# canAIReSensor.net
KiCad netlist of a schematic drawn in EAGLE
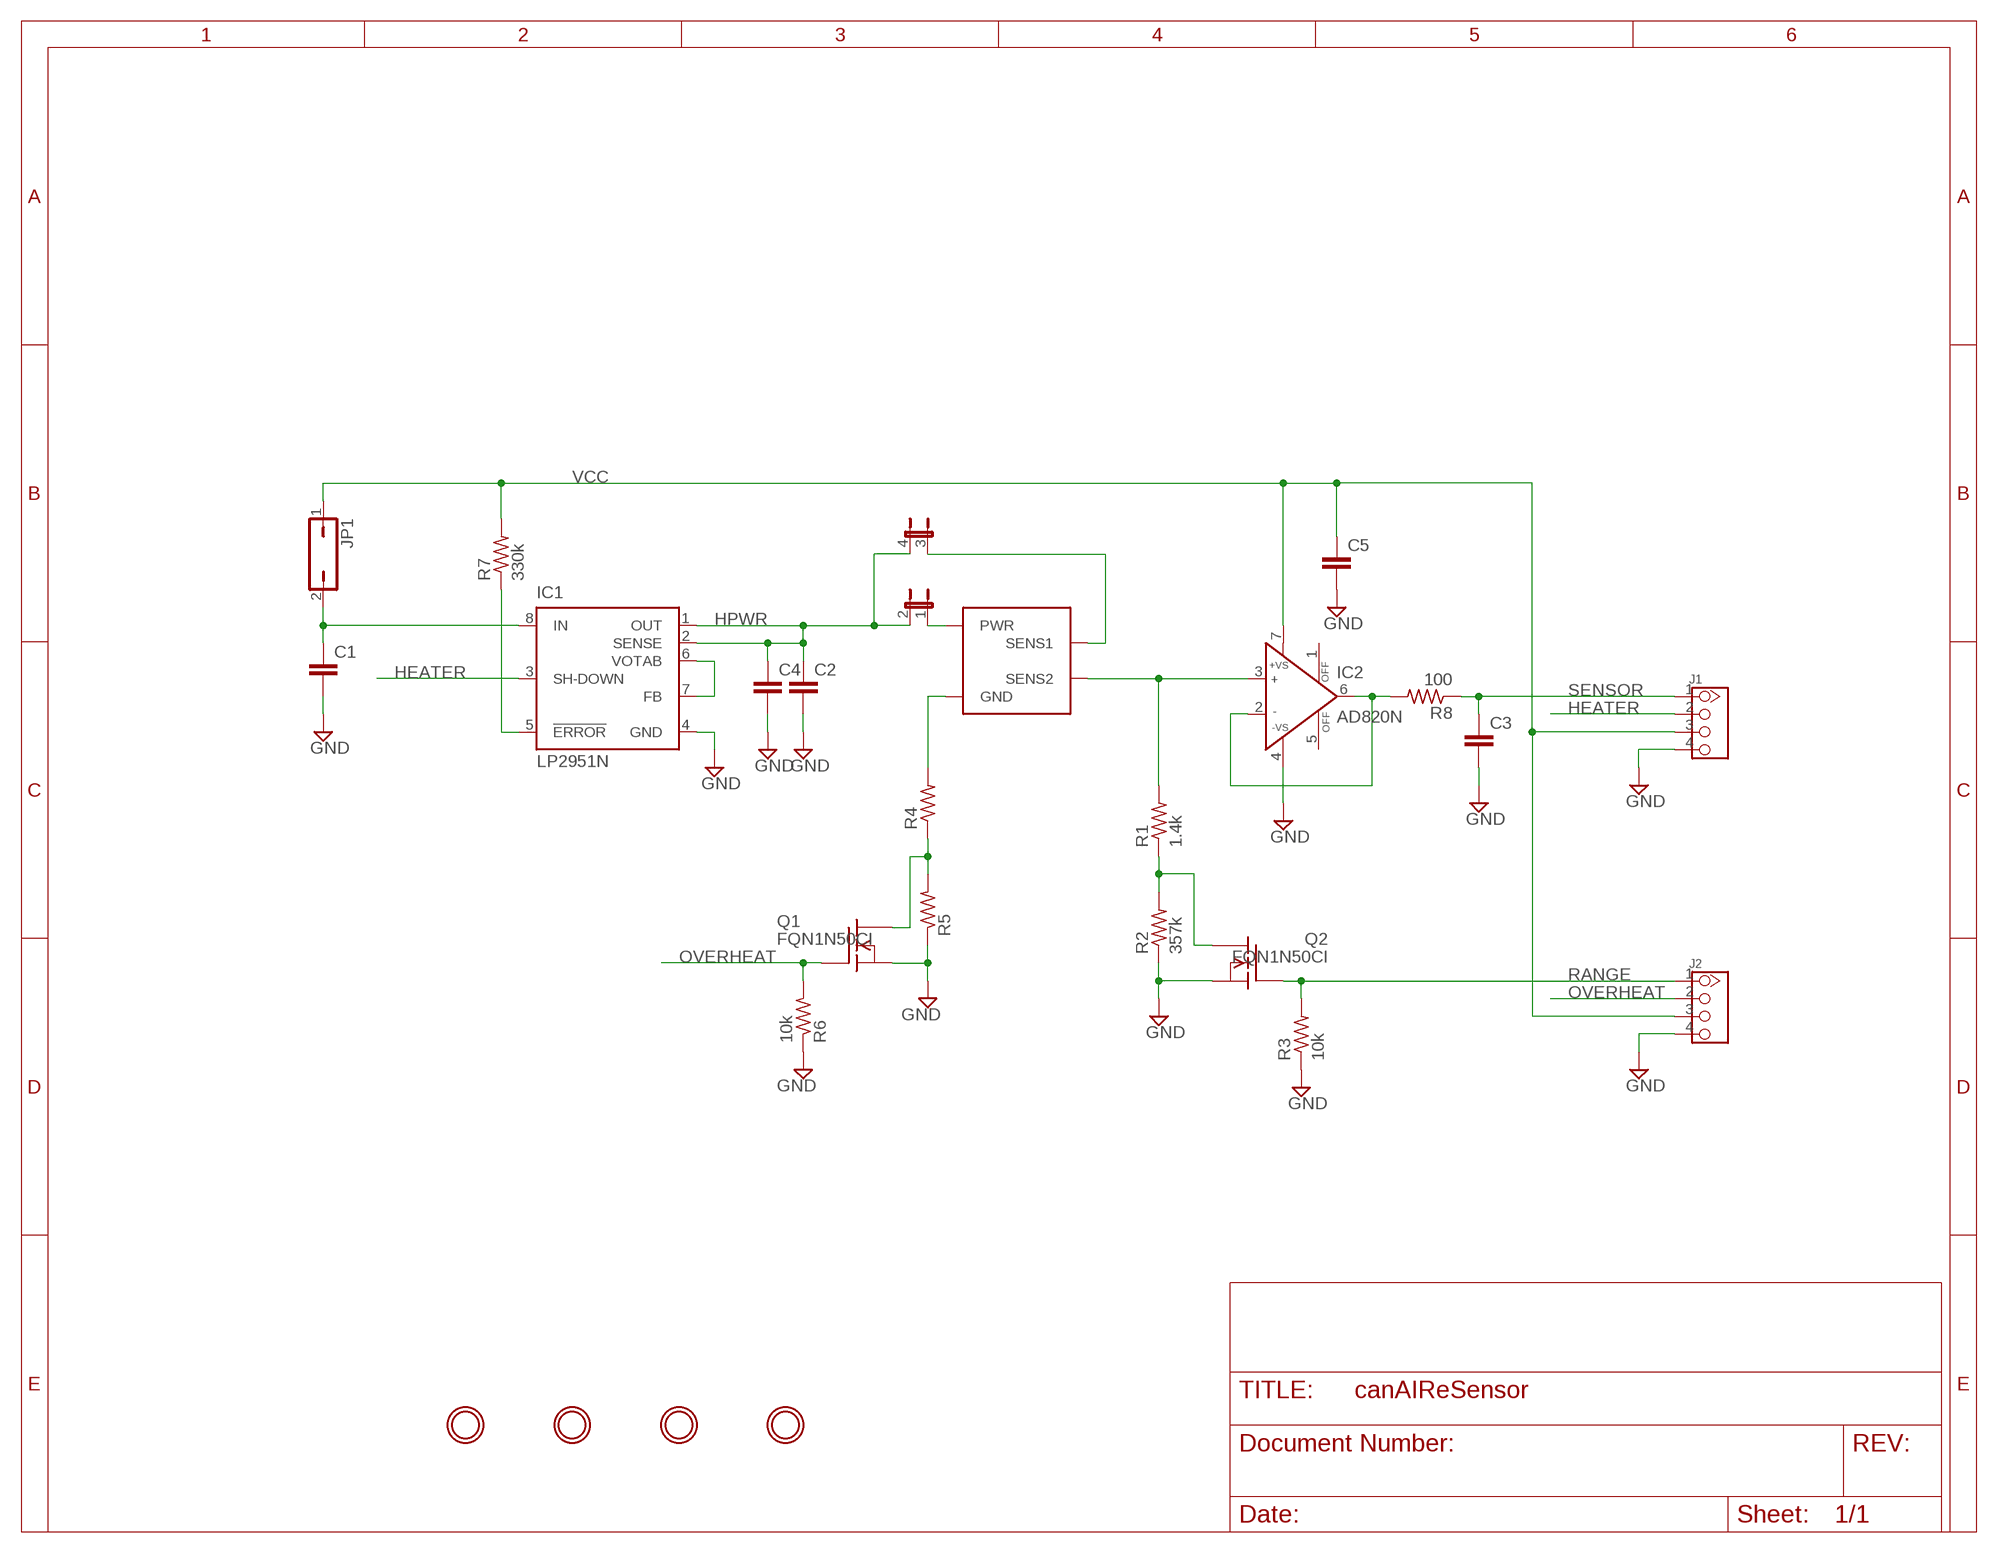
[diagram p0: schematic, sheet 1]

(export (version "E")
  (design (tool "Eeschema 10.0.6"))
  (components
    (comp (ref "C1")
      (value "C-EU050-024X044")
      (footprint "eagle-import:C050-024X044")
      (libsource (lib "eagle-import") (part "C-EU050-024X044"))
    )
    (comp (ref "C2")
      (value "C-EU050-024X044")
      (footprint "eagle-import:C050-024X044")
      (libsource (lib "eagle-import") (part "C-EU050-024X044"))
    )
    (comp (ref "C3")
      (value "C-EU050-024X044")
      (footprint "eagle-import:C050-024X044")
      (libsource (lib "eagle-import") (part "C-EU050-024X044"))
    )
    (comp (ref "C4")
      (value "C-EU050-024X044")
      (footprint "eagle-import:C050-024X044")
      (libsource (lib "eagle-import") (part "C-EU050-024X044"))
    )
    (comp (ref "C5")
      (value "C-EU050-024X044")
      (footprint "eagle-import:C050-024X044")
      (libsource (lib "eagle-import") (part "C-EU050-024X044"))
    )
    (comp (ref "IC1")
      (value "LP2951N")
      (footprint "eagle-import:DIL08")
      (libsource (lib "eagle-import") (part "LP2951N"))
    )
    (comp (ref "IC2")
      (value "AD820N")
      (footprint "eagle-import:DIL08")
      (libsource (lib "eagle-import") (part "AD820N"))
    )
    (comp (ref "J1")
      (value "TWIG-4P-2.0'90D'")
      (footprint "eagle-import:4P-2.0-90D")
      (libsource (lib "eagle-import") (part "TWIG-4P-2.0'90D'"))
    )
    (comp (ref "J2")
      (value "TWIG-4P-2.0'90D'")
      (footprint "eagle-import:4P-2.0-90D")
      (libsource (lib "eagle-import") (part "TWIG-4P-2.0'90D'"))
    )
    (comp (ref "JP1")
      (value "JP1Q")
      (footprint "eagle-import:JP1")
      (libsource (lib "eagle-import") (part "JP1Q"))
    )
    (comp (ref "JP4")
      (value "JP2QE")
      (footprint "eagle-import:JP2Q")
      (libsource (lib "eagle-import") (part "JP2QE"))
    )
    (comp (ref "Q1")
      (value "FQN1N50CI")
      (footprint "eagle-import:TO92-INLINE")
      (libsource (lib "eagle-import") (part "FQN1N50CI"))
    )
    (comp (ref "Q2")
      (value "FQN1N50CI")
      (footprint "eagle-import:TO92-INLINE")
      (libsource (lib "eagle-import") (part "FQN1N50CI"))
    )
    (comp (ref "R1")
      (value "1.4k")
      (footprint "eagle-import:0204_7")
      (libsource (lib "eagle-import") (part "R-US_0204/7"))
    )
    (comp (ref "R2")
      (value "357k")
      (footprint "eagle-import:0204_7")
      (libsource (lib "eagle-import") (part "R-US_0204/7"))
    )
    (comp (ref "R3")
      (value "10k")
      (footprint "eagle-import:0204_7")
      (libsource (lib "eagle-import") (part "R-US_0204/7"))
    )
    (comp (ref "R4")
      (value "R-US_0204/7")
      (footprint "eagle-import:0204_7")
      (libsource (lib "eagle-import") (part "R-US_0204/7"))
    )
    (comp (ref "R5")
      (value "R-US_0204/7")
      (footprint "eagle-import:0204_7")
      (libsource (lib "eagle-import") (part "R-US_0204/7"))
    )
    (comp (ref "R6")
      (value "10k")
      (footprint "eagle-import:0204_7")
      (libsource (lib "eagle-import") (part "R-US_0204/7"))
    )
    (comp (ref "R7")
      (value "330k")
      (footprint "eagle-import:0204_7")
      (libsource (lib "eagle-import") (part "R-US_0204/7"))
    )
    (comp (ref "R8")
      (value "100")
      (footprint "eagle-import:0204_7")
      (libsource (lib "eagle-import") (part "R-US_0204/7"))
    )
    (comp (ref "U$1")
      (value "E2V_MICS")
      (footprint "eagle-import:E2V_MICS")
      (libsource (lib "eagle-import") (part "E2V_MICS"))
    )
    (comp (ref "U$2")
      (value "MOUNTINGHOLE2.5")
      (footprint "eagle-import:MOUNTINGHOLE_2.5_PLATED")
      (libsource (lib "eagle-import") (part "MOUNTINGHOLE2.5"))
    )
    (comp (ref "U$3")
      (value "MOUNTINGHOLE2.5")
      (footprint "eagle-import:MOUNTINGHOLE_2.5_PLATED")
      (libsource (lib "eagle-import") (part "MOUNTINGHOLE2.5"))
    )
    (comp (ref "U$4")
      (value "MOUNTINGHOLE2.5")
      (footprint "eagle-import:MOUNTINGHOLE_2.5_PLATED")
      (libsource (lib "eagle-import") (part "MOUNTINGHOLE2.5"))
    )
    (comp (ref "U$5")
      (value "MOUNTINGHOLE2.5")
      (footprint "eagle-import:MOUNTINGHOLE_2.5_PLATED")
      (libsource (lib "eagle-import") (part "MOUNTINGHOLE2.5"))
    )
  )
  (nets
    (net (code "1") (name "/HEATER") (class "Default")
      (node (ref "IC1") (pin "3") (pinfunction "SH-DOWN_3") (pintype "input"))
      (node (ref "J1") (pin "2") (pinfunction "2_2") (pintype "bidirectional"))
    )
    (net (code "2") (name "/HPWR") (class "Default")
      (node (ref "C2") (pin "1") (pinfunction "1_1") (pintype "passive"))
      (node (ref "C4") (pin "1") (pinfunction "1_1") (pintype "passive"))
      (node (ref "IC1") (pin "1") (pinfunction "OUT_1") (pintype "input"))
      (node (ref "IC1") (pin "2") (pinfunction "SENSE_2") (pintype "input"))
      (node (ref "JP4") (pin "2") (pinfunction "2_2") (pintype "passive"))
      (node (ref "JP4") (pin "4") (pinfunction "2_4") (pintype "passive"))
    )
    (net (code "3") (name "/OVERHEAT") (class "Default")
      (node (ref "J2") (pin "2") (pinfunction "2_2") (pintype "bidirectional"))
      (node (ref "Q1") (pin "2") (pinfunction "G_2") (pintype "passive"))
      (node (ref "R6") (pin "2") (pinfunction "2_2") (pintype "passive"))
    )
    (net (code "4") (name "/RANGE") (class "Default")
      (node (ref "J2") (pin "1") (pinfunction "1_1") (pintype "bidirectional"))
      (node (ref "Q2") (pin "2") (pinfunction "G_2") (pintype "passive"))
      (node (ref "R3") (pin "2") (pinfunction "2_2") (pintype "passive"))
    )
    (net (code "5") (name "/SENSOR") (class "Default")
      (node (ref "C3") (pin "1") (pinfunction "1_1") (pintype "passive"))
      (node (ref "J1") (pin "1") (pinfunction "1_1") (pintype "bidirectional"))
      (node (ref "R8") (pin "1") (pinfunction "1_1") (pintype "passive"))
    )
    (net (code "6") (name "/VCC") (class "Default")
      (node (ref "C5") (pin "1") (pinfunction "1_1") (pintype "passive"))
      (node (ref "IC2") (pin "7") (pinfunction "+VS_7") (pintype "input"))
      (node (ref "J1") (pin "3") (pinfunction "3_3") (pintype "bidirectional"))
      (node (ref "J2") (pin "3") (pinfunction "3_3") (pintype "bidirectional"))
      (node (ref "JP1") (pin "1") (pinfunction "1_1") (pintype "passive"))
      (node (ref "R7") (pin "2") (pinfunction "2_2") (pintype "passive"))
    )
    (net (code "7") (name "GND") (class "Default")
      (node (ref "C1") (pin "2") (pinfunction "2_2") (pintype "passive"))
      (node (ref "C2") (pin "2") (pinfunction "2_2") (pintype "passive"))
      (node (ref "C3") (pin "2") (pinfunction "2_2") (pintype "passive"))
      (node (ref "C4") (pin "2") (pinfunction "2_2") (pintype "passive"))
      (node (ref "C5") (pin "2") (pinfunction "2_2") (pintype "passive"))
      (node (ref "IC1") (pin "4") (pinfunction "GND_4") (pintype "power_in"))
      (node (ref "IC2") (pin "4") (pinfunction "-VS_4") (pintype "input"))
      (node (ref "J1") (pin "4") (pinfunction "4_4") (pintype "bidirectional"))
      (node (ref "J2") (pin "4") (pinfunction "4_4") (pintype "bidirectional"))
      (node (ref "Q1") (pin "3") (pinfunction "S_3") (pintype "passive"))
      (node (ref "Q2") (pin "3") (pinfunction "S_3") (pintype "passive"))
      (node (ref "R2") (pin "1") (pinfunction "1_1") (pintype "passive"))
      (node (ref "R3") (pin "1") (pinfunction "1_1") (pintype "passive"))
      (node (ref "R5") (pin "1") (pinfunction "1_1") (pintype "passive"))
      (node (ref "R6") (pin "1") (pinfunction "1_1") (pintype "passive"))
    )
    (net (code "8") (name "Net-(IC1-FB)") (class "Default")
      (node (ref "IC1") (pin "6") (pinfunction "VOTAB_6") (pintype "passive"))
      (node (ref "IC1") (pin "7") (pinfunction "FB_7") (pintype "input"))
    )
    (net (code "9") (name "Net-(IC1-IN)") (class "Default")
      (node (ref "C1") (pin "1") (pinfunction "1_1") (pintype "passive"))
      (node (ref "IC1") (pin "8") (pinfunction "IN_8") (pintype "input"))
      (node (ref "JP1") (pin "2") (pinfunction "2_2") (pintype "passive"))
    )
    (net (code "10") (name "Net-(IC1-~{ERROR})") (class "Default")
      (node (ref "IC1") (pin "5") (pinfunction "~{ERROR}_5") (pintype "output"))
      (node (ref "R7") (pin "1") (pinfunction "1_1") (pintype "passive"))
    )
    (net (code "11") (name "Net-(IC2-IN+)") (class "Default")
      (node (ref "IC2") (pin "3") (pinfunction "IN+_3") (pintype "input"))
      (node (ref "R1") (pin "2") (pinfunction "2_2") (pintype "passive"))
      (node (ref "U$1") (pin "2") (pinfunction "SENS2_2") (pintype "passive"))
    )
    (net (code "12") (name "Net-(IC2-IN-)") (class "Default")
      (node (ref "IC2") (pin "2") (pinfunction "IN-_2") (pintype "input"))
      (node (ref "IC2") (pin "6") (pinfunction "OUT_6") (pintype "output"))
      (node (ref "R8") (pin "2") (pinfunction "2_2") (pintype "passive"))
    )
    (net (code "13") (name "Net-(JP4B-1)") (class "Default")
      (node (ref "JP4") (pin "3") (pinfunction "1_3") (pintype "passive"))
      (node (ref "U$1") (pin "4") (pinfunction "SENS1_4") (pintype "passive"))
    )
    (net (code "14") (name "Net-(Q1-D)") (class "Default")
      (node (ref "Q1") (pin "1") (pinfunction "D_1") (pintype "passive"))
      (node (ref "R4") (pin "1") (pinfunction "1_1") (pintype "passive"))
      (node (ref "R5") (pin "2") (pinfunction "2_2") (pintype "passive"))
    )
    (net (code "15") (name "Net-(Q2-D)") (class "Default")
      (node (ref "Q2") (pin "1") (pinfunction "D_1") (pintype "passive"))
      (node (ref "R1") (pin "1") (pinfunction "1_1") (pintype "passive"))
      (node (ref "R2") (pin "2") (pinfunction "2_2") (pintype "passive"))
    )
    (net (code "16") (name "Net-(U$1-GND)") (class "Default")
      (node (ref "R4") (pin "2") (pinfunction "2_2") (pintype "passive"))
      (node (ref "U$1") (pin "1") (pinfunction "GND_1") (pintype "power_in"))
    )
    (net (code "17") (name "Net-(U$1-PWR)") (class "Default")
      (node (ref "JP4") (pin "1") (pinfunction "1_1") (pintype "passive"))
      (node (ref "U$1") (pin "3") (pinfunction "PWR_3") (pintype "power_in"))
    )
    (net (code "18") (name "unconnected-(IC2-OFF-Pad1)") (class "Default")
      (node (ref "IC2") (pin "1") (pinfunction "OFF_1") (pintype "passive"))
    )
    (net (code "19") (name "unconnected-(IC2-OFF-Pad5)") (class "Default")
      (node (ref "IC2") (pin "5") (pinfunction "OFF_5") (pintype "passive"))
    )
  )
)
